# 201_3axisRev010100.net
KiCad netlist of a schematic drawn in EAGLE
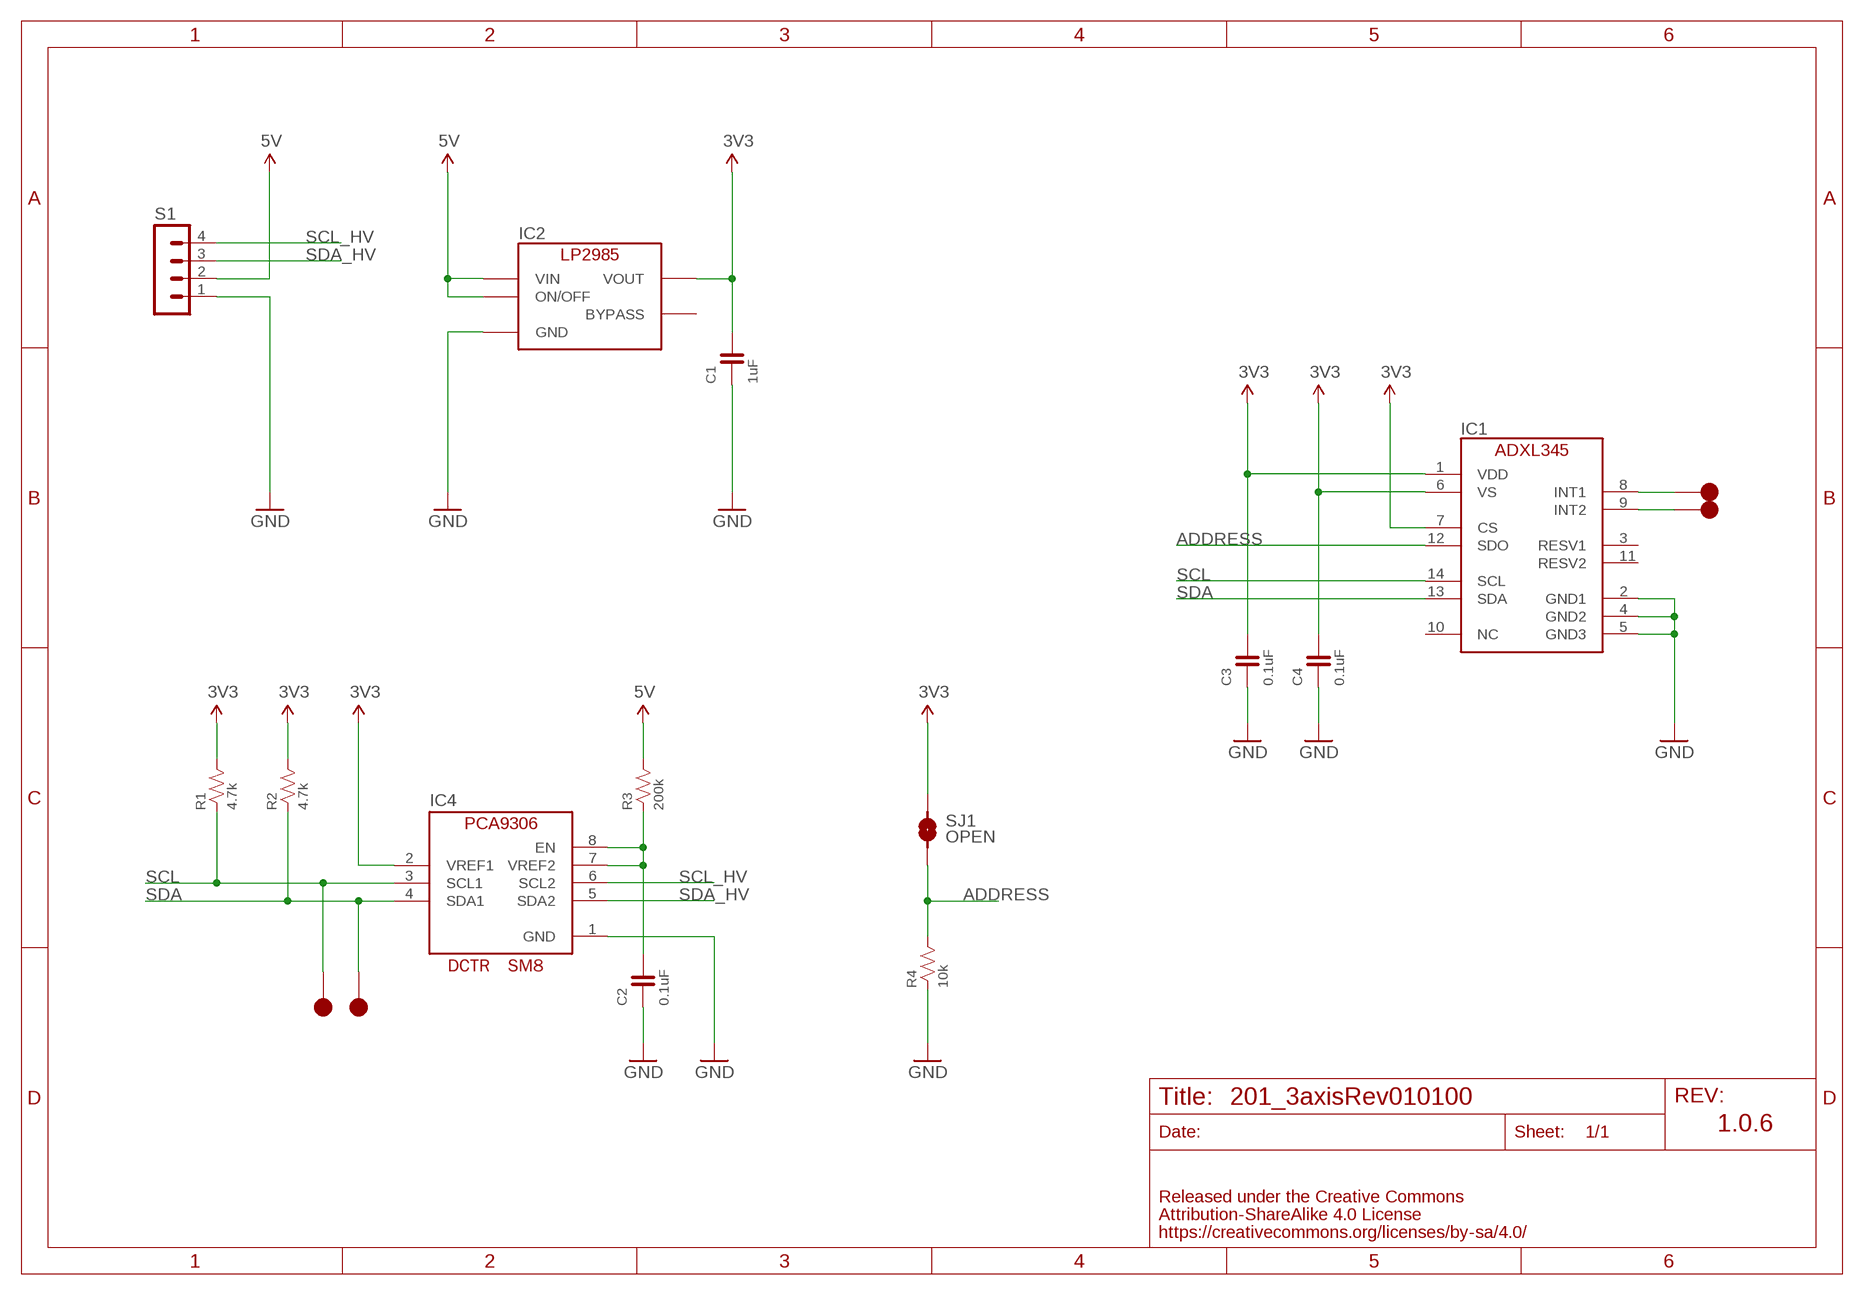
[diagram p0: schematic, sheet 1]

(export (version "E")
  (design (tool "Eeschema 10.0.6"))
  (components
    (comp (ref "C1")
      (value "1uF")
      (footprint "eagle-import:0603")
      (libsource (lib "eagle-import") (part "CAPACITOR-0603"))
    )
    (comp (ref "C2")
      (value "0.1uF")
      (footprint "eagle-import:0603")
      (libsource (lib "eagle-import") (part "CAPACITOR-0603"))
    )
    (comp (ref "C3")
      (value "0.1uF")
      (footprint "eagle-import:0603")
      (libsource (lib "eagle-import") (part "CAPACITOR-0603"))
    )
    (comp (ref "C4")
      (value "0.1uF")
      (footprint "eagle-import:0603")
      (libsource (lib "eagle-import") (part "CAPACITOR-0603"))
    )
    (comp (ref "IC1")
      (value "AD-ADXL345")
      (footprint "eagle-import:ANALOGDEVICES-ADXL345")
      (libsource (lib "eagle-import") (part "AD-ADXL345"))
    )
    (comp (ref "IC2")
      (value "LP2985-33DBV")
      (footprint "eagle-import:SOT-23-5")
      (libsource (lib "eagle-import") (part "LP2985-33DBV"))
    )
    (comp (ref "IC4")
      (value "PCA9306_SSOP")
      (footprint "eagle-import:8PIN-SSOP")
      (libsource (lib "eagle-import") (part "PCA9306_SSOP"))
    )
    (comp (ref "R1")
      (value "4.7k")
      (footprint "eagle-import:0603")
      (libsource (lib "eagle-import") (part "RESISTOR-0603"))
    )
    (comp (ref "R2")
      (value "4.7k")
      (footprint "eagle-import:0603")
      (libsource (lib "eagle-import") (part "RESISTOR-0603"))
    )
    (comp (ref "R3")
      (value "200k")
      (footprint "eagle-import:0603")
      (libsource (lib "eagle-import") (part "RESISTOR-0603"))
    )
    (comp (ref "R4")
      (value "10k")
      (footprint "eagle-import:0603")
      (libsource (lib "eagle-import") (part "RESISTOR-0603"))
    )
    (comp (ref "S1")
      (value "MA04-1")
      (footprint "eagle-import:MA04-1")
      (libsource (lib "eagle-import") (part "MA04-1"))
    )
    (comp (ref "SJ1")
      (value "OPEN")
      (footprint "eagle-import:SMD-JUMPER-2")
      (libsource (lib "eagle-import") (part "SMD-JUMPER-2"))
    )
    (comp (ref "TP1")
      (value "TP-15")
      (footprint "eagle-import:TP-15")
      (libsource (lib "eagle-import") (part "TP-15"))
    )
    (comp (ref "TP2")
      (value "TP-15")
      (footprint "eagle-import:TP-15")
      (libsource (lib "eagle-import") (part "TP-15"))
    )
    (comp (ref "TP3")
      (value "TP-15")
      (footprint "eagle-import:TP-15")
      (libsource (lib "eagle-import") (part "TP-15"))
    )
    (comp (ref "TP4")
      (value "TP-15")
      (footprint "eagle-import:TP-15")
      (libsource (lib "eagle-import") (part "TP-15"))
    )
  )
  (nets
    (net (code "1") (name "/ADDRESS") (class "Default")
      (node (ref "IC1") (pin "12") (pinfunction "SDO_12") (pintype "bidirectional"))
      (node (ref "R4") (pin "2") (pinfunction "2_2") (pintype "bidirectional"))
      (node (ref "SJ1") (pin "2") (pinfunction "2_2") (pintype "passive"))
    )
    (net (code "2") (name "/SCL") (class "Default")
      (node (ref "IC1") (pin "14") (pinfunction "SCL_14") (pintype "bidirectional"))
      (node (ref "IC4") (pin "3") (pinfunction "SCL1_3") (pintype "bidirectional"))
      (node (ref "R1") (pin "1") (pinfunction "1_1") (pintype "bidirectional"))
      (node (ref "TP2") (pin "1") (pinfunction "1_1") (pintype "bidirectional"))
    )
    (net (code "3") (name "/SCL_HV") (class "Default")
      (node (ref "IC4") (pin "6") (pinfunction "SCL2_6") (pintype "bidirectional"))
      (node (ref "S1") (pin "4") (pinfunction "4_4") (pintype "passive"))
    )
    (net (code "4") (name "/SDA") (class "Default")
      (node (ref "IC1") (pin "13") (pinfunction "SDA_13") (pintype "bidirectional"))
      (node (ref "IC4") (pin "4") (pinfunction "SDA1_4") (pintype "bidirectional"))
      (node (ref "R2") (pin "1") (pinfunction "1_1") (pintype "bidirectional"))
      (node (ref "TP1") (pin "1") (pinfunction "1_1") (pintype "bidirectional"))
    )
    (net (code "5") (name "/SDA_HV") (class "Default")
      (node (ref "IC4") (pin "5") (pinfunction "SDA2_5") (pintype "bidirectional"))
      (node (ref "S1") (pin "3") (pinfunction "3_3") (pintype "passive"))
    )
    (net (code "6") (name "3V3") (class "Default")
      (node (ref "C1") (pin "2") (pinfunction "2_2") (pintype "passive"))
      (node (ref "C3") (pin "2") (pinfunction "2_2") (pintype "passive"))
      (node (ref "C4") (pin "2") (pinfunction "2_2") (pintype "passive"))
      (node (ref "IC1") (pin "1") (pinfunction "VDD_1") (pintype "bidirectional"))
      (node (ref "IC1") (pin "6") (pinfunction "VS_6") (pintype "bidirectional"))
      (node (ref "IC1") (pin "7") (pinfunction "CS_7") (pintype "bidirectional"))
      (node (ref "IC2") (pin "5") (pinfunction "VOUT_5") (pintype "output"))
      (node (ref "IC4") (pin "2") (pinfunction "VREF1_2") (pintype "bidirectional"))
      (node (ref "R1") (pin "2") (pinfunction "2_2") (pintype "bidirectional"))
      (node (ref "R2") (pin "2") (pinfunction "2_2") (pintype "bidirectional"))
      (node (ref "SJ1") (pin "1") (pinfunction "1_1") (pintype "passive"))
    )
    (net (code "7") (name "5V") (class "Default")
      (node (ref "IC2") (pin "1") (pinfunction "VIN_1") (pintype "input"))
      (node (ref "IC2") (pin "3") (pinfunction "ON/OFF_3") (pintype "input"))
      (node (ref "R3") (pin "2") (pinfunction "2_2") (pintype "bidirectional"))
      (node (ref "S1") (pin "2") (pinfunction "2_2") (pintype "passive"))
    )
    (net (code "8") (name "GND") (class "Default")
      (node (ref "C1") (pin "1") (pinfunction "1_1") (pintype "passive"))
      (node (ref "C2") (pin "1") (pinfunction "1_1") (pintype "passive"))
      (node (ref "C3") (pin "1") (pinfunction "1_1") (pintype "passive"))
      (node (ref "C4") (pin "1") (pinfunction "1_1") (pintype "passive"))
      (node (ref "IC1") (pin "2") (pinfunction "GND1_2") (pintype "bidirectional"))
      (node (ref "IC1") (pin "4") (pinfunction "GND2_4") (pintype "bidirectional"))
      (node (ref "IC1") (pin "5") (pinfunction "GND3_5") (pintype "bidirectional"))
      (node (ref "IC2") (pin "2") (pinfunction "GND_2") (pintype "power_in"))
      (node (ref "IC4") (pin "1") (pinfunction "GND_1") (pintype "bidirectional"))
      (node (ref "R4") (pin "1") (pinfunction "1_1") (pintype "bidirectional"))
      (node (ref "S1") (pin "1") (pinfunction "1_1") (pintype "passive"))
    )
    (net (code "9") (name "Net-(IC1-INT1)") (class "Default")
      (node (ref "IC1") (pin "8") (pinfunction "INT1_8") (pintype "bidirectional"))
      (node (ref "TP3") (pin "1") (pinfunction "1_1") (pintype "bidirectional"))
    )
    (net (code "10") (name "Net-(IC1-INT2)") (class "Default")
      (node (ref "IC1") (pin "9") (pinfunction "INT2_9") (pintype "bidirectional"))
      (node (ref "TP4") (pin "1") (pinfunction "1_1") (pintype "bidirectional"))
    )
    (net (code "11") (name "Net-(IC4-EN)") (class "Default")
      (node (ref "C2") (pin "2") (pinfunction "2_2") (pintype "passive"))
      (node (ref "IC4") (pin "7") (pinfunction "VREF2_7") (pintype "bidirectional"))
      (node (ref "IC4") (pin "8") (pinfunction "EN_8") (pintype "bidirectional"))
      (node (ref "R3") (pin "1") (pinfunction "1_1") (pintype "bidirectional"))
    )
    (net (code "12") (name "unconnected-(IC1-NC-Pad10)") (class "Default")
      (node (ref "IC1") (pin "10") (pinfunction "NC_10") (pintype "bidirectional"))
    )
    (net (code "13") (name "unconnected-(IC1-RESV1-Pad3)") (class "Default")
      (node (ref "IC1") (pin "3") (pinfunction "RESV1_3") (pintype "bidirectional"))
    )
    (net (code "14") (name "unconnected-(IC1-RESV2-Pad11)") (class "Default")
      (node (ref "IC1") (pin "11") (pinfunction "RESV2_11") (pintype "bidirectional"))
    )
    (net (code "15") (name "unconnected-(IC2-BYPASS-Pad4)") (class "Default")
      (node (ref "IC2") (pin "4") (pinfunction "BYPASS_4") (pintype "bidirectional"))
    )
  )
)
